# Laser.net
KiCad netlist of a schematic drawn in Altium Designer
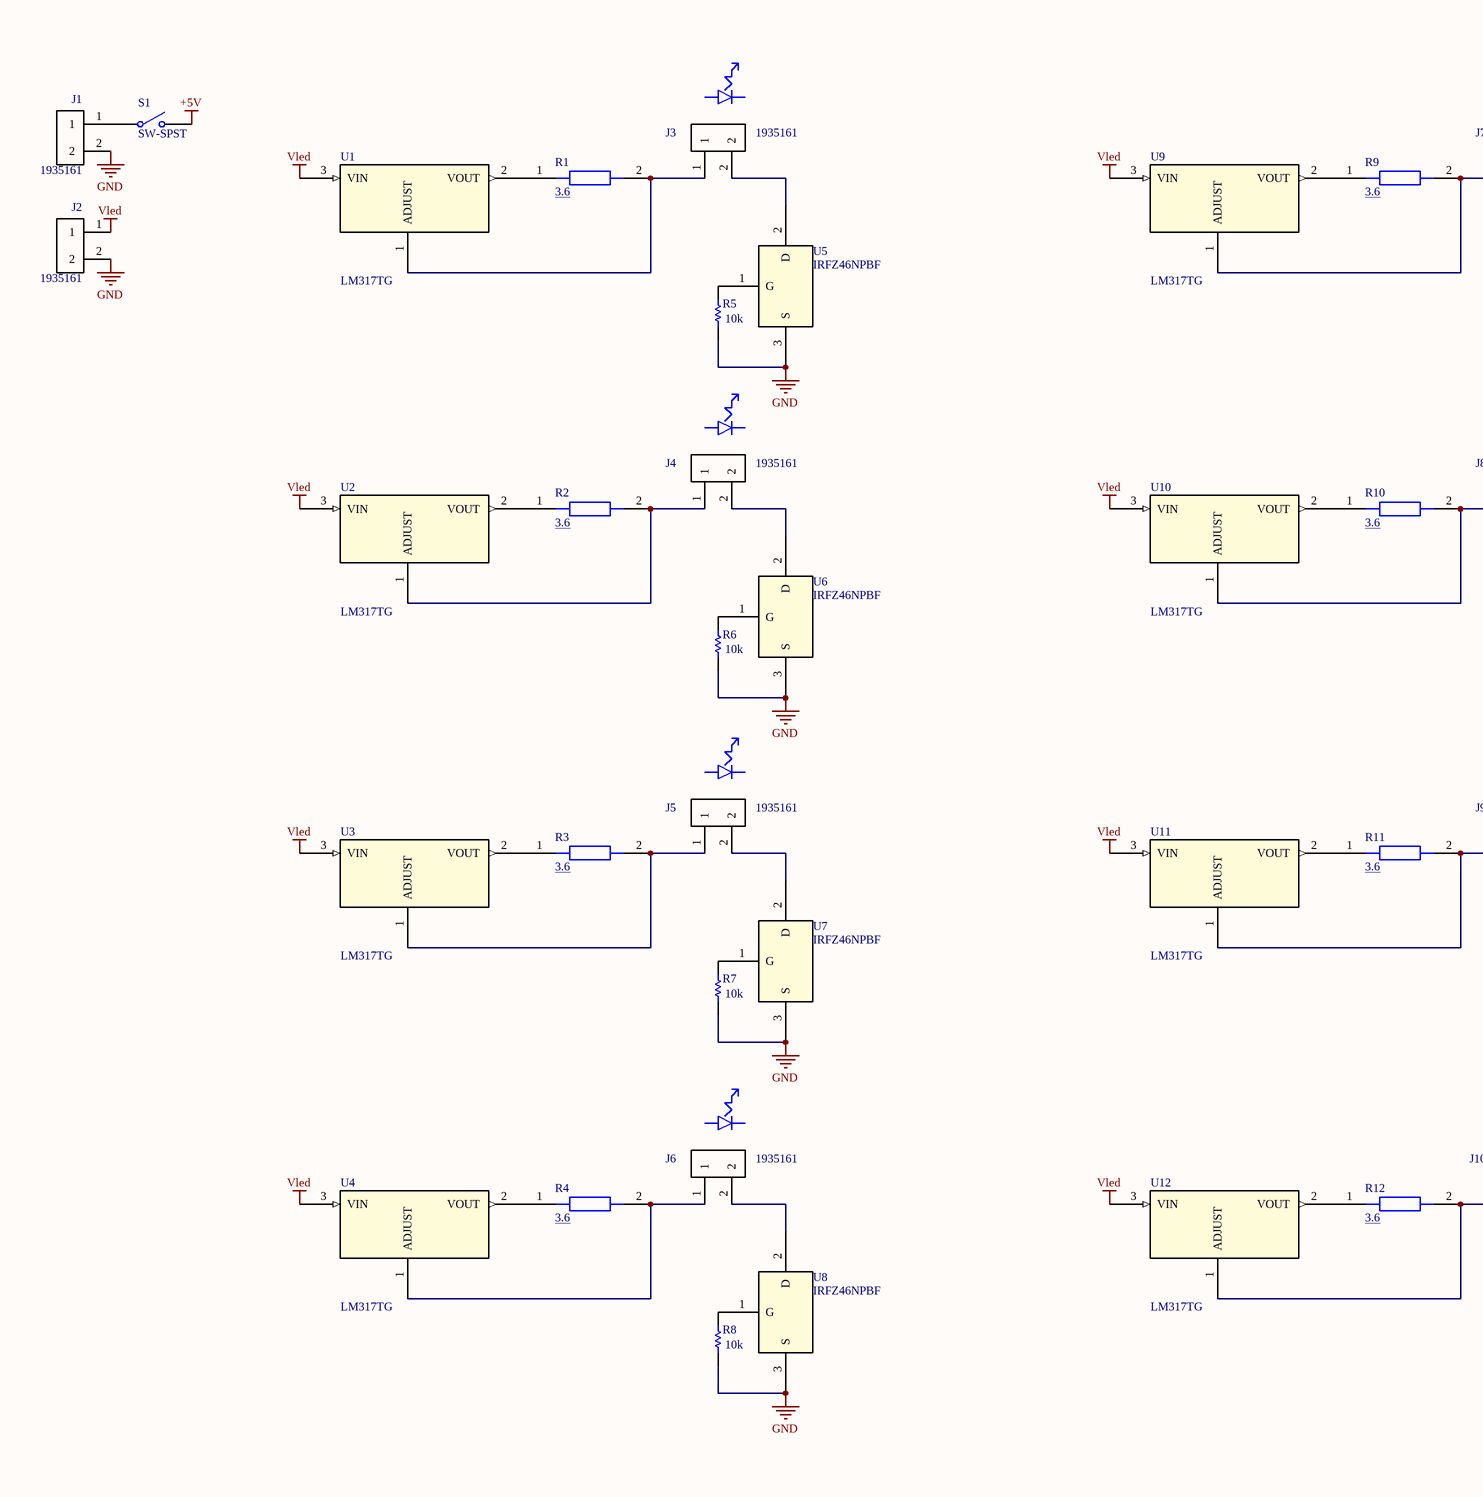
[diagram p0: Laser.SchDoc, left]
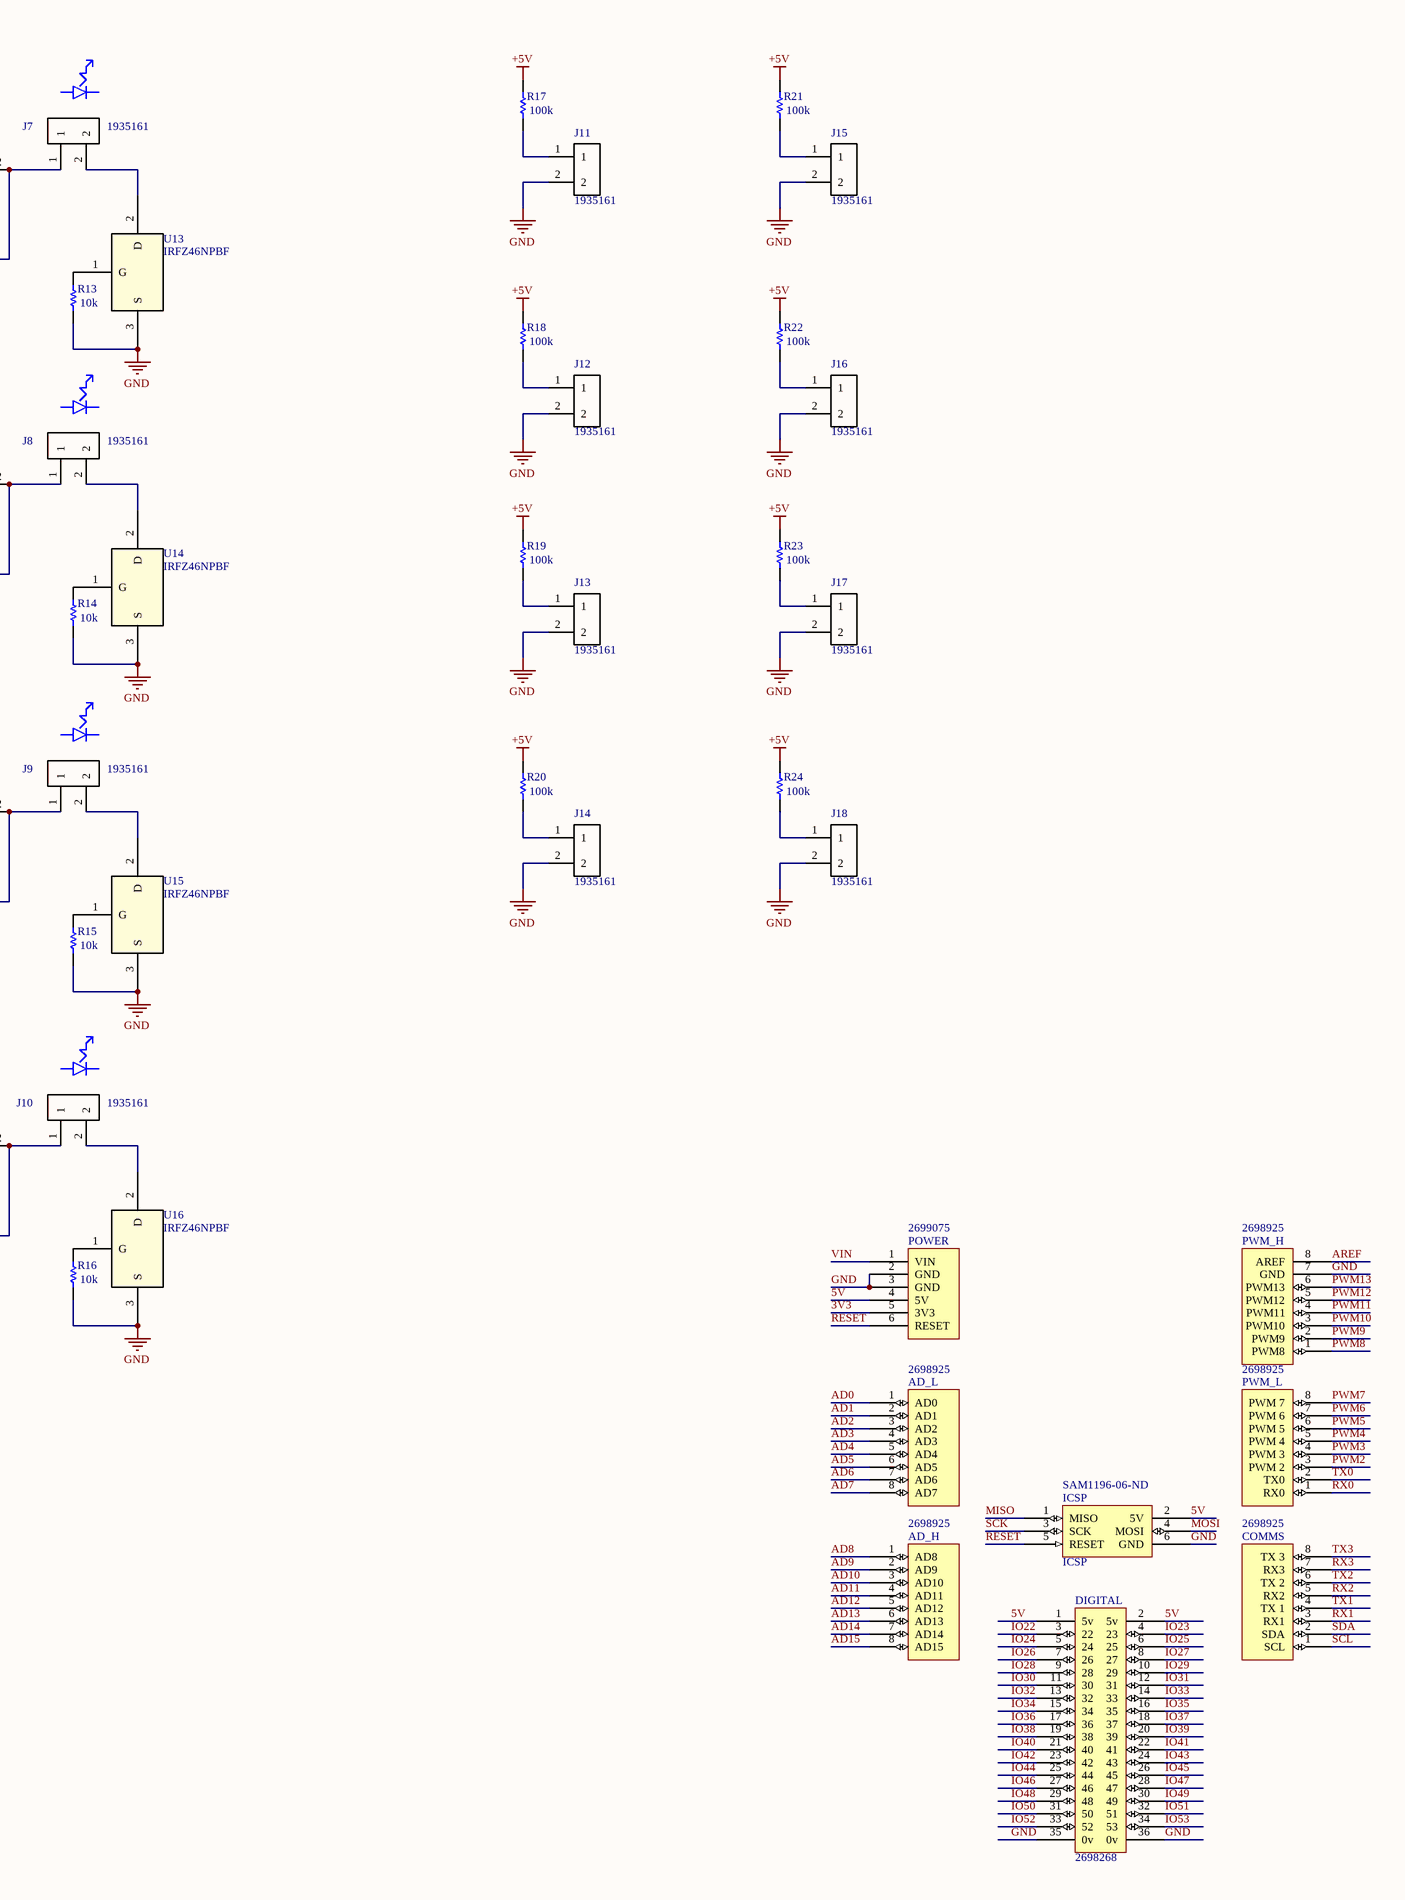
[diagram p1: Laser.SchDoc, right]

(export (version "E")
  (design (tool "Eeschema 10.0.6"))
  (components
    (comp (ref "AD_H")
      (value "AD_H")
      (footprint "Header 8x1 8.5mm")
      (fields (field (name "SUPPLIER PART NUMBER 4") "2698925"))
      (libsource (lib "Header") (part "AD_H"))
    )
    (comp (ref "AD_L")
      (value "AD_L")
      (footprint "Header 8x1 8.5mm")
      (fields (field (name "SUPPLIER PART NUMBER 5") "2698925"))
      (libsource (lib "Header") (part "AD_L"))
    )
    (comp (ref "COMMS")
      (value "Communication")
      (footprint "Header 8x1 8.5mm")
      (fields (field (name "SUPPLIER PART NUMBER 4") "2698925"))
      (libsource (lib "Header") (part "Communication"))
    )
    (comp (ref "DIGITAL")
      (value "IO_36")
      (footprint "HEADER 36X 8MM")
      (fields (field (name "SUPPLIER PART NUMBER 5") "2698268"))
      (libsource (lib "Header") (part "IO_36"))
    )
    (comp (ref "ICSP")
      (value "ICSP")
      (footprint "ICSP")
      (fields (field (name "SUPPLIER PART NUMBER 5") "SAM1196-06-ND"))
      (libsource (lib "Header") (part "ICSP"))
    )
    (comp (ref "J1")
      (value "1935161")
      (footprint "PHOENIX_1935161")
      (description "Conn Terminal Blocks 2 POS 5mm Solder ST Thru-Hole 16A")
      (fields (field (name "DIGI-KEY_PART_NUMBER") "277-1667-ND") (field (name "MF") "Phoenix Contact"))
      (libsource (lib "Laser") (part "1935161"))
    )
    (comp (ref "J2")
      (value "1935161")
      (footprint "PHOENIX_1935161")
      (description "Conn Terminal Blocks 2 POS 5mm Solder ST Thru-Hole 16A")
      (fields (field (name "DIGI-KEY_PART_NUMBER") "277-1667-ND") (field (name "MF") "Phoenix Contact"))
      (libsource (lib "Laser") (part "1935161"))
    )
    (comp (ref "J3")
      (value "1935161")
      (footprint "PHOENIX_1935161")
      (description "Conn Terminal Blocks 2 POS 5mm Solder ST Thru-Hole 16A")
      (fields (field (name "DIGI-KEY_PART_NUMBER") "277-1667-ND") (field (name "MF") "Phoenix Contact"))
      (libsource (lib "Laser") (part "1935161"))
    )
    (comp (ref "J4")
      (value "1935161")
      (footprint "PHOENIX_1935161")
      (description "Conn Terminal Blocks 2 POS 5mm Solder ST Thru-Hole 16A")
      (fields (field (name "DIGI-KEY_PART_NUMBER") "277-1667-ND") (field (name "MF") "Phoenix Contact"))
      (libsource (lib "Laser") (part "1935161"))
    )
    (comp (ref "J5")
      (value "1935161")
      (footprint "PHOENIX_1935161")
      (description "Conn Terminal Blocks 2 POS 5mm Solder ST Thru-Hole 16A")
      (fields (field (name "DIGI-KEY_PART_NUMBER") "277-1667-ND") (field (name "MF") "Phoenix Contact"))
      (libsource (lib "Laser") (part "1935161"))
    )
    (comp (ref "J6")
      (value "1935161")
      (footprint "PHOENIX_1935161")
      (description "Conn Terminal Blocks 2 POS 5mm Solder ST Thru-Hole 16A")
      (fields (field (name "DIGI-KEY_PART_NUMBER") "277-1667-ND") (field (name "MF") "Phoenix Contact"))
      (libsource (lib "Laser") (part "1935161"))
    )
    (comp (ref "J7")
      (value "1935161")
      (footprint "PHOENIX_1935161")
      (description "Conn Terminal Blocks 2 POS 5mm Solder ST Thru-Hole 16A")
      (fields (field (name "DIGI-KEY_PART_NUMBER") "277-1667-ND") (field (name "MF") "Phoenix Contact"))
      (libsource (lib "Laser") (part "1935161"))
    )
    (comp (ref "J8")
      (value "1935161")
      (footprint "PHOENIX_1935161")
      (description "Conn Terminal Blocks 2 POS 5mm Solder ST Thru-Hole 16A")
      (fields (field (name "DIGI-KEY_PART_NUMBER") "277-1667-ND") (field (name "MF") "Phoenix Contact"))
      (libsource (lib "Laser") (part "1935161"))
    )
    (comp (ref "J9")
      (value "1935161")
      (footprint "PHOENIX_1935161")
      (description "Conn Terminal Blocks 2 POS 5mm Solder ST Thru-Hole 16A")
      (fields (field (name "DIGI-KEY_PART_NUMBER") "277-1667-ND") (field (name "MF") "Phoenix Contact"))
      (libsource (lib "Laser") (part "1935161"))
    )
    (comp (ref "J10")
      (value "1935161")
      (footprint "PHOENIX_1935161")
      (description "Conn Terminal Blocks 2 POS 5mm Solder ST Thru-Hole 16A")
      (fields (field (name "DIGI-KEY_PART_NUMBER") "277-1667-ND") (field (name "MF") "Phoenix Contact"))
      (libsource (lib "Laser") (part "1935161"))
    )
    (comp (ref "J11")
      (value "1935161")
      (footprint "PHOENIX_1935161")
      (description "Conn Terminal Blocks 2 POS 5mm Solder ST Thru-Hole 16A")
      (fields (field (name "DIGI-KEY_PART_NUMBER") "277-1667-ND") (field (name "MF") "Phoenix Contact"))
      (libsource (lib "Laser") (part "1935161"))
    )
    (comp (ref "J12")
      (value "1935161")
      (footprint "PHOENIX_1935161")
      (description "Conn Terminal Blocks 2 POS 5mm Solder ST Thru-Hole 16A")
      (fields (field (name "DIGI-KEY_PART_NUMBER") "277-1667-ND") (field (name "MF") "Phoenix Contact"))
      (libsource (lib "Laser") (part "1935161"))
    )
    (comp (ref "J13")
      (value "1935161")
      (footprint "PHOENIX_1935161")
      (description "Conn Terminal Blocks 2 POS 5mm Solder ST Thru-Hole 16A")
      (fields (field (name "DIGI-KEY_PART_NUMBER") "277-1667-ND") (field (name "MF") "Phoenix Contact"))
      (libsource (lib "Laser") (part "1935161"))
    )
    (comp (ref "J14")
      (value "1935161")
      (footprint "PHOENIX_1935161")
      (description "Conn Terminal Blocks 2 POS 5mm Solder ST Thru-Hole 16A")
      (fields (field (name "DIGI-KEY_PART_NUMBER") "277-1667-ND") (field (name "MF") "Phoenix Contact"))
      (libsource (lib "Laser") (part "1935161"))
    )
    (comp (ref "J15")
      (value "1935161")
      (footprint "PHOENIX_1935161")
      (description "Conn Terminal Blocks 2 POS 5mm Solder ST Thru-Hole 16A")
      (fields (field (name "DIGI-KEY_PART_NUMBER") "277-1667-ND") (field (name "MF") "Phoenix Contact"))
      (libsource (lib "Laser") (part "1935161"))
    )
    (comp (ref "J16")
      (value "1935161")
      (footprint "PHOENIX_1935161")
      (description "Conn Terminal Blocks 2 POS 5mm Solder ST Thru-Hole 16A")
      (fields (field (name "DIGI-KEY_PART_NUMBER") "277-1667-ND") (field (name "MF") "Phoenix Contact"))
      (libsource (lib "Laser") (part "1935161"))
    )
    (comp (ref "J17")
      (value "1935161")
      (footprint "PHOENIX_1935161")
      (description "Conn Terminal Blocks 2 POS 5mm Solder ST Thru-Hole 16A")
      (fields (field (name "DIGI-KEY_PART_NUMBER") "277-1667-ND") (field (name "MF") "Phoenix Contact"))
      (libsource (lib "Laser") (part "1935161"))
    )
    (comp (ref "J18")
      (value "1935161")
      (footprint "PHOENIX_1935161")
      (description "Conn Terminal Blocks 2 POS 5mm Solder ST Thru-Hole 16A")
      (fields (field (name "DIGI-KEY_PART_NUMBER") "277-1667-ND") (field (name "MF") "Phoenix Contact"))
      (libsource (lib "Laser") (part "1935161"))
    )
    (comp (ref "POWER")
      (value "POWER")
      (footprint "Header 6x1 8.5mm")
      (fields (field (name "SUPPLIER PART NUMBER 2") "2699075"))
      (libsource (lib "Header") (part "POWER"))
    )
    (comp (ref "PWM_H")
      (value "PWM_H")
      (footprint "Header 8x1 8.5mm")
      (fields (field (name "SUPPLIER PART NUMBER 4") "2698925"))
      (libsource (lib "Header") (part "PWM_H"))
    )
    (comp (ref "PWM_L")
      (value "PWM_L")
      (footprint "Header 8x1 8.5mm")
      (fields (field (name "SUPPLIER PART NUMBER 4") "2698925"))
      (libsource (lib "Header") (part "PWM_L"))
    )
    (comp (ref "R1") (value "3.6") (footprint "3.6_R") (libsource (lib "Laser") (part "3.6")))
    (comp (ref "R2") (value "3.6") (footprint "3.6_R") (libsource (lib "Laser") (part "3.6")))
    (comp (ref "R3") (value "3.6") (footprint "3.6_R") (libsource (lib "Laser") (part "3.6")))
    (comp (ref "R4") (value "3.6") (footprint "3.6_R") (libsource (lib "Laser") (part "3.6")))
    (comp (ref "R5")
      (value "10k")
      (footprint "AXIAL-0.3")
      (description "Resistor")
      (fields (field (name "Comment") "Res1") (field (name "PUBLISHER") "Altium Limited"))
      (libsource (lib "Miscellaneous Devices") (part "Res1"))
    )
    (comp (ref "R6")
      (value "10k")
      (footprint "AXIAL-0.3")
      (description "Resistor")
      (fields (field (name "Comment") "Res1") (field (name "PUBLISHER") "Altium Limited"))
      (libsource (lib "Miscellaneous Devices") (part "Res1"))
    )
    (comp (ref "R7")
      (value "10k")
      (footprint "AXIAL-0.3")
      (description "Resistor")
      (fields (field (name "Comment") "Res1") (field (name "PUBLISHER") "Altium Limited"))
      (libsource (lib "Miscellaneous Devices") (part "Res1"))
    )
    (comp (ref "R8")
      (value "10k")
      (footprint "AXIAL-0.3")
      (description "Resistor")
      (fields (field (name "Comment") "Res1") (field (name "PUBLISHER") "Altium Limited"))
      (libsource (lib "Miscellaneous Devices") (part "Res1"))
    )
    (comp (ref "R9") (value "3.6") (footprint "3.6_R") (libsource (lib "Laser") (part "3.6")))
    (comp (ref "R10") (value "3.6") (footprint "3.6_R") (libsource (lib "Laser") (part "3.6")))
    (comp (ref "R11") (value "3.6") (footprint "3.6_R") (libsource (lib "Laser") (part "3.6")))
    (comp (ref "R12") (value "3.6") (footprint "3.6_R") (libsource (lib "Laser") (part "3.6")))
    (comp (ref "R13")
      (value "10k")
      (footprint "AXIAL-0.3")
      (description "Resistor")
      (fields (field (name "Comment") "Res1") (field (name "PUBLISHER") "Altium Limited"))
      (libsource (lib "Miscellaneous Devices") (part "Res1"))
    )
    (comp (ref "R14")
      (value "10k")
      (footprint "AXIAL-0.3")
      (description "Resistor")
      (fields (field (name "Comment") "Res1") (field (name "PUBLISHER") "Altium Limited"))
      (libsource (lib "Miscellaneous Devices") (part "Res1"))
    )
    (comp (ref "R15")
      (value "10k")
      (footprint "AXIAL-0.3")
      (description "Resistor")
      (fields (field (name "Comment") "Res1") (field (name "PUBLISHER") "Altium Limited"))
      (libsource (lib "Miscellaneous Devices") (part "Res1"))
    )
    (comp (ref "R16")
      (value "10k")
      (footprint "AXIAL-0.3")
      (description "Resistor")
      (fields (field (name "Comment") "Res1") (field (name "PUBLISHER") "Altium Limited"))
      (libsource (lib "Miscellaneous Devices") (part "Res1"))
    )
    (comp (ref "R17")
      (value "100k")
      (footprint "AXIAL-0.3")
      (description "Resistor")
      (fields (field (name "Comment") "Res1") (field (name "PUBLISHER") "Altium Limited"))
      (libsource (lib "Miscellaneous Devices") (part "Res1"))
    )
    (comp (ref "R18")
      (value "100k")
      (footprint "AXIAL-0.3")
      (description "Resistor")
      (fields (field (name "Comment") "Res1") (field (name "PUBLISHER") "Altium Limited"))
      (libsource (lib "Miscellaneous Devices") (part "Res1"))
    )
    (comp (ref "R19")
      (value "100k")
      (footprint "AXIAL-0.3")
      (description "Resistor")
      (fields (field (name "Comment") "Res1") (field (name "PUBLISHER") "Altium Limited"))
      (libsource (lib "Miscellaneous Devices") (part "Res1"))
    )
    (comp (ref "R20")
      (value "100k")
      (footprint "AXIAL-0.3")
      (description "Resistor")
      (fields (field (name "Comment") "Res1") (field (name "PUBLISHER") "Altium Limited"))
      (libsource (lib "Miscellaneous Devices") (part "Res1"))
    )
    (comp (ref "R21")
      (value "100k")
      (footprint "AXIAL-0.3")
      (description "Resistor")
      (fields (field (name "Comment") "Res1") (field (name "PUBLISHER") "Altium Limited"))
      (libsource (lib "Miscellaneous Devices") (part "Res1"))
    )
    (comp (ref "R22")
      (value "100k")
      (footprint "AXIAL-0.3")
      (description "Resistor")
      (fields (field (name "Comment") "Res1") (field (name "PUBLISHER") "Altium Limited"))
      (libsource (lib "Miscellaneous Devices") (part "Res1"))
    )
    (comp (ref "R23")
      (value "100k")
      (footprint "AXIAL-0.3")
      (description "Resistor")
      (fields (field (name "Comment") "Res1") (field (name "PUBLISHER") "Altium Limited"))
      (libsource (lib "Miscellaneous Devices") (part "Res1"))
    )
    (comp (ref "R24")
      (value "100k")
      (footprint "AXIAL-0.3")
      (description "Resistor")
      (fields (field (name "Comment") "Res1") (field (name "PUBLISHER") "Altium Limited"))
      (libsource (lib "Miscellaneous Devices") (part "Res1"))
    )
    (comp (ref "S1")
      (value "SW-SPST")
      (footprint "SPST-2")
      (description "Single-Pole, Single-Throw Switch")
      (fields (field (name "PUBLISHER") "Altium Limited"))
      (libsource (lib "Miscellaneous Devices") (part "SW-SPST"))
    )
    (comp (ref "U1")
      (value "LM317TG")
      (footprint "TO-220AB")
      (description "Imported")
      (libsource (lib "Laser") (part "LM317TG"))
    )
    (comp (ref "U2")
      (value "LM317TG")
      (footprint "TO-220AB")
      (description "Imported")
      (libsource (lib "Laser") (part "LM317TG"))
    )
    (comp (ref "U3")
      (value "LM317TG")
      (footprint "TO-220AB")
      (description "Imported")
      (libsource (lib "Laser") (part "LM317TG"))
    )
    (comp (ref "U4")
      (value "LM317TG")
      (footprint "TO-220AB")
      (description "Imported")
      (libsource (lib "Laser") (part "LM317TG"))
    )
    (comp (ref "U5")
      (value "IRFZ46NPBF")
      (footprint "TO-220AB")
      (description "Imported")
      (libsource (lib "Laser") (part "IRFZ46NPBF"))
    )
    (comp (ref "U6")
      (value "IRFZ46NPBF")
      (footprint "TO-220AB")
      (description "Imported")
      (libsource (lib "Laser") (part "IRFZ46NPBF"))
    )
    (comp (ref "U7")
      (value "IRFZ46NPBF")
      (footprint "TO-220AB")
      (description "Imported")
      (libsource (lib "Laser") (part "IRFZ46NPBF"))
    )
    (comp (ref "U8")
      (value "IRFZ46NPBF")
      (footprint "TO-220AB")
      (description "Imported")
      (libsource (lib "Laser") (part "IRFZ46NPBF"))
    )
    (comp (ref "U9")
      (value "LM317TG")
      (footprint "TO-220AB")
      (description "Imported")
      (libsource (lib "Laser") (part "LM317TG"))
    )
    (comp (ref "U10")
      (value "LM317TG")
      (footprint "TO-220AB")
      (description "Imported")
      (libsource (lib "Laser") (part "LM317TG"))
    )
    (comp (ref "U11")
      (value "LM317TG")
      (footprint "TO-220AB")
      (description "Imported")
      (libsource (lib "Laser") (part "LM317TG"))
    )
    (comp (ref "U12")
      (value "LM317TG")
      (footprint "TO-220AB")
      (description "Imported")
      (libsource (lib "Laser") (part "LM317TG"))
    )
    (comp (ref "U13")
      (value "IRFZ46NPBF")
      (footprint "TO-220AB")
      (description "Imported")
      (libsource (lib "Laser") (part "IRFZ46NPBF"))
    )
    (comp (ref "U14")
      (value "IRFZ46NPBF")
      (footprint "TO-220AB")
      (description "Imported")
      (libsource (lib "Laser") (part "IRFZ46NPBF"))
    )
    (comp (ref "U15")
      (value "IRFZ46NPBF")
      (footprint "TO-220AB")
      (description "Imported")
      (libsource (lib "Laser") (part "IRFZ46NPBF"))
    )
    (comp (ref "U16")
      (value "IRFZ46NPBF")
      (footprint "TO-220AB")
      (description "Imported")
      (libsource (lib "Laser") (part "IRFZ46NPBF"))
    )
  )
  (nets
    (net (code "1") (name "+5V") (class "Default")
      (node (ref "R17") (pin "2") (pinfunction "2_2") (pintype "passive"))
      (node (ref "R18") (pin "2") (pinfunction "2_2") (pintype "passive"))
      (node (ref "R19") (pin "2") (pinfunction "2_2") (pintype "passive"))
      (node (ref "R20") (pin "2") (pinfunction "2_2") (pintype "passive"))
      (node (ref "R21") (pin "2") (pinfunction "2_2") (pintype "passive"))
      (node (ref "R22") (pin "2") (pinfunction "2_2") (pintype "passive"))
      (node (ref "R23") (pin "2") (pinfunction "2_2") (pintype "passive"))
      (node (ref "R24") (pin "2") (pinfunction "2_2") (pintype "passive"))
      (node (ref "S1") (pin "2") (pinfunction "NO_2") (pintype "passive"))
    )
    (net (code "2") (name "/3V3") (class "Default")
      (node (ref "POWER") (pin "5") (pinfunction "3V3_5") (pintype "power_in"))
    )
    (net (code "3") (name "/5V") (class "Default")
      (node (ref "DIGITAL") (pin "1") (pinfunction "5v_1") (pintype "power_in"))
      (node (ref "DIGITAL") (pin "2") (pinfunction "5v_2") (pintype "power_in"))
      (node (ref "ICSP") (pin "2") (pinfunction "5V_2") (pintype "power_in"))
      (node (ref "POWER") (pin "4") (pinfunction "5V_4") (pintype "power_in"))
    )
    (net (code "4") (name "/AD0") (class "Default")
      (node (ref "AD_L") (pin "1") (pinfunction "AD0_1") (pintype "bidirectional"))
    )
    (net (code "5") (name "/AD1") (class "Default")
      (node (ref "AD_L") (pin "2") (pinfunction "AD1_2") (pintype "bidirectional"))
    )
    (net (code "6") (name "/AD2") (class "Default")
      (node (ref "AD_L") (pin "3") (pinfunction "AD2_3") (pintype "bidirectional"))
    )
    (net (code "7") (name "/AD3") (class "Default")
      (node (ref "AD_L") (pin "4") (pinfunction "AD3_4") (pintype "bidirectional"))
    )
    (net (code "8") (name "/AD4") (class "Default")
      (node (ref "AD_L") (pin "5") (pinfunction "AD4_5") (pintype "bidirectional"))
    )
    (net (code "9") (name "/AD5") (class "Default")
      (node (ref "AD_L") (pin "6") (pinfunction "AD5_6") (pintype "bidirectional"))
    )
    (net (code "10") (name "/AD6") (class "Default")
      (node (ref "AD_L") (pin "7") (pinfunction "AD6_7") (pintype "bidirectional"))
    )
    (net (code "11") (name "/AD7") (class "Default")
      (node (ref "AD_L") (pin "8") (pinfunction "AD7_8") (pintype "bidirectional"))
    )
    (net (code "12") (name "/AD8") (class "Default")
      (node (ref "AD_H") (pin "1") (pinfunction "AD8_1") (pintype "bidirectional"))
    )
    (net (code "13") (name "/AD9") (class "Default")
      (node (ref "AD_H") (pin "2") (pinfunction "AD9_2") (pintype "bidirectional"))
    )
    (net (code "14") (name "/AD10") (class "Default")
      (node (ref "AD_H") (pin "3") (pinfunction "AD10_3") (pintype "bidirectional"))
    )
    (net (code "15") (name "/AD11") (class "Default")
      (node (ref "AD_H") (pin "4") (pinfunction "AD11_4") (pintype "bidirectional"))
    )
    (net (code "16") (name "/AD12") (class "Default")
      (node (ref "AD_H") (pin "5") (pinfunction "AD12_5") (pintype "bidirectional"))
    )
    (net (code "17") (name "/AD13") (class "Default")
      (node (ref "AD_H") (pin "6") (pinfunction "AD13_6") (pintype "bidirectional"))
    )
    (net (code "18") (name "/AD14") (class "Default")
      (node (ref "AD_H") (pin "7") (pinfunction "AD14_7") (pintype "bidirectional"))
    )
    (net (code "19") (name "/AD15") (class "Default")
      (node (ref "AD_H") (pin "8") (pinfunction "AD15_8") (pintype "bidirectional"))
    )
    (net (code "20") (name "/AREF") (class "Default")
      (node (ref "PWM_H") (pin "8") (pinfunction "AREF_8") (pintype "passive"))
    )
    (net (code "21") (name "/IO22") (class "Default")
      (node (ref "DIGITAL") (pin "3") (pinfunction "22_3") (pintype "bidirectional"))
    )
    (net (code "22") (name "/IO23") (class "Default")
      (node (ref "DIGITAL") (pin "4") (pinfunction "23_4") (pintype "bidirectional"))
    )
    (net (code "23") (name "/IO24") (class "Default")
      (node (ref "DIGITAL") (pin "5") (pinfunction "24_5") (pintype "bidirectional"))
    )
    (net (code "24") (name "/IO25") (class "Default")
      (node (ref "DIGITAL") (pin "6") (pinfunction "25_6") (pintype "bidirectional"))
    )
    (net (code "25") (name "/IO26") (class "Default")
      (node (ref "DIGITAL") (pin "7") (pinfunction "26_7") (pintype "bidirectional"))
    )
    (net (code "26") (name "/IO27") (class "Default")
      (node (ref "DIGITAL") (pin "8") (pinfunction "27_8") (pintype "bidirectional"))
    )
    (net (code "27") (name "/IO28") (class "Default")
      (node (ref "DIGITAL") (pin "9") (pinfunction "28_9") (pintype "bidirectional"))
    )
    (net (code "28") (name "/IO29") (class "Default")
      (node (ref "DIGITAL") (pin "10") (pinfunction "29_10") (pintype "bidirectional"))
    )
    (net (code "29") (name "/IO30") (class "Default")
      (node (ref "DIGITAL") (pin "11") (pinfunction "30_11") (pintype "bidirectional"))
    )
    (net (code "30") (name "/IO31") (class "Default")
      (node (ref "DIGITAL") (pin "12") (pinfunction "31_12") (pintype "bidirectional"))
    )
    (net (code "31") (name "/IO32") (class "Default")
      (node (ref "DIGITAL") (pin "13") (pinfunction "32_13") (pintype "bidirectional"))
    )
    (net (code "32") (name "/IO33") (class "Default")
      (node (ref "DIGITAL") (pin "14") (pinfunction "33_14") (pintype "bidirectional"))
    )
    (net (code "33") (name "/IO34") (class "Default")
      (node (ref "DIGITAL") (pin "15") (pinfunction "34_15") (pintype "bidirectional"))
    )
    (net (code "34") (name "/IO35") (class "Default")
      (node (ref "DIGITAL") (pin "16") (pinfunction "35_16") (pintype "bidirectional"))
    )
    (net (code "35") (name "/IO36") (class "Default")
      (node (ref "DIGITAL") (pin "17") (pinfunction "36_17") (pintype "bidirectional"))
    )
    (net (code "36") (name "/IO37") (class "Default")
      (node (ref "DIGITAL") (pin "18") (pinfunction "37_18") (pintype "bidirectional"))
    )
    (net (code "37") (name "/IO38") (class "Default")
      (node (ref "DIGITAL") (pin "19") (pinfunction "38_19") (pintype "bidirectional"))
    )
    (net (code "38") (name "/IO39") (class "Default")
      (node (ref "DIGITAL") (pin "20") (pinfunction "39_20") (pintype "bidirectional"))
    )
    (net (code "39") (name "/IO40") (class "Default")
      (node (ref "DIGITAL") (pin "21") (pinfunction "40_21") (pintype "bidirectional"))
    )
    (net (code "40") (name "/IO41") (class "Default")
      (node (ref "DIGITAL") (pin "22") (pinfunction "41_22") (pintype "bidirectional"))
    )
    (net (code "41") (name "/IO42") (class "Default")
      (node (ref "DIGITAL") (pin "23") (pinfunction "42_23") (pintype "bidirectional"))
    )
    (net (code "42") (name "/IO43") (class "Default")
      (node (ref "DIGITAL") (pin "24") (pinfunction "43_24") (pintype "bidirectional"))
    )
    (net (code "43") (name "/IO44") (class "Default")
      (node (ref "DIGITAL") (pin "25") (pinfunction "44_25") (pintype "bidirectional"))
    )
    (net (code "44") (name "/IO45") (class "Default")
      (node (ref "DIGITAL") (pin "26") (pinfunction "45_26") (pintype "bidirectional"))
    )
    (net (code "45") (name "/IO46") (class "Default")
      (node (ref "DIGITAL") (pin "27") (pinfunction "46_27") (pintype "bidirectional"))
    )
    (net (code "46") (name "/IO47") (class "Default")
      (node (ref "DIGITAL") (pin "28") (pinfunction "47_28") (pintype "bidirectional"))
    )
    (net (code "47") (name "/IO48") (class "Default")
      (node (ref "DIGITAL") (pin "29") (pinfunction "48_29") (pintype "bidirectional"))
    )
    (net (code "48") (name "/IO49") (class "Default")
      (node (ref "DIGITAL") (pin "30") (pinfunction "49_30") (pintype "bidirectional"))
    )
    (net (code "49") (name "/IO50") (class "Default")
      (node (ref "DIGITAL") (pin "31") (pinfunction "50_31") (pintype "bidirectional"))
    )
    (net (code "50") (name "/IO51") (class "Default")
      (node (ref "DIGITAL") (pin "32") (pinfunction "51_32") (pintype "bidirectional"))
    )
    (net (code "51") (name "/IO52") (class "Default")
      (node (ref "DIGITAL") (pin "33") (pinfunction "52_33") (pintype "bidirectional"))
    )
    (net (code "52") (name "/IO53") (class "Default")
      (node (ref "DIGITAL") (pin "34") (pinfunction "53_34") (pintype "bidirectional"))
    )
    (net (code "53") (name "/MISO") (class "Default")
      (node (ref "ICSP") (pin "1") (pinfunction "MISO_1") (pintype "bidirectional"))
    )
    (net (code "54") (name "/MOSI") (class "Default")
      (node (ref "ICSP") (pin "4") (pinfunction "MOSI_4") (pintype "bidirectional"))
    )
    (net (code "55") (name "/PWM2") (class "Default")
      (node (ref "PWM_L") (pin "3") (pinfunction "PWM_2_3") (pintype "bidirectional"))
    )
    (net (code "56") (name "/PWM3") (class "Default")
      (node (ref "PWM_L") (pin "4") (pinfunction "PWM_3_4") (pintype "bidirectional"))
    )
    (net (code "57") (name "/PWM4") (class "Default")
      (node (ref "PWM_L") (pin "5") (pinfunction "PWM_4_5") (pintype "bidirectional"))
    )
    (net (code "58") (name "/PWM5") (class "Default")
      (node (ref "PWM_L") (pin "6") (pinfunction "PWM_5_6") (pintype "bidirectional"))
    )
    (net (code "59") (name "/PWM6") (class "Default")
      (node (ref "PWM_L") (pin "7") (pinfunction "PWM_6_7") (pintype "bidirectional"))
    )
    (net (code "60") (name "/PWM7") (class "Default")
      (node (ref "PWM_L") (pin "8") (pinfunction "PWM_7_8") (pintype "bidirectional"))
    )
    (net (code "61") (name "/PWM8") (class "Default")
      (node (ref "PWM_H") (pin "1") (pinfunction "PWM8_1") (pintype "bidirectional"))
    )
    (net (code "62") (name "/PWM9") (class "Default")
      (node (ref "PWM_H") (pin "2") (pinfunction "PWM9_2") (pintype "bidirectional"))
    )
    (net (code "63") (name "/PWM10") (class "Default")
      (node (ref "PWM_H") (pin "3") (pinfunction "PWM10_3") (pintype "bidirectional"))
    )
    (net (code "64") (name "/PWM11") (class "Default")
      (node (ref "PWM_H") (pin "4") (pinfunction "PWM11_4") (pintype "bidirectional"))
    )
    (net (code "65") (name "/PWM12") (class "Default")
      (node (ref "PWM_H") (pin "5") (pinfunction "PWM12_5") (pintype "bidirectional"))
    )
    (net (code "66") (name "/PWM13") (class "Default")
      (node (ref "PWM_H") (pin "6") (pinfunction "PWM13_6") (pintype "bidirectional"))
    )
    (net (code "67") (name "/RESET") (class "Default")
      (node (ref "ICSP") (pin "5") (pinfunction "RESET_5") (pintype "input"))
      (node (ref "POWER") (pin "6") (pinfunction "RESET_6") (pintype "passive"))
    )
    (net (code "68") (name "/RX0") (class "Default")
      (node (ref "PWM_L") (pin "1") (pinfunction "RX0_1") (pintype "bidirectional"))
    )
    (net (code "69") (name "/RX1") (class "Default")
      (node (ref "COMMS") (pin "3") (pinfunction "RX1_3") (pintype "bidirectional"))
    )
    (net (code "70") (name "/RX2") (class "Default")
      (node (ref "COMMS") (pin "5") (pinfunction "RX2_5") (pintype "bidirectional"))
    )
    (net (code "71") (name "/RX3") (class "Default")
      (node (ref "COMMS") (pin "7") (pinfunction "RX3_7") (pintype "bidirectional"))
    )
    (net (code "72") (name "/SCK") (class "Default")
      (node (ref "ICSP") (pin "3") (pinfunction "SCK_3") (pintype "bidirectional"))
    )
    (net (code "73") (name "/SCL") (class "Default")
      (node (ref "COMMS") (pin "1") (pinfunction "SCL_1") (pintype "bidirectional"))
    )
    (net (code "74") (name "/SDA") (class "Default")
      (node (ref "COMMS") (pin "2") (pinfunction "SDA_2") (pintype "bidirectional"))
    )
    (net (code "75") (name "/TX0") (class "Default")
      (node (ref "PWM_L") (pin "2") (pinfunction "TX0_2") (pintype "bidirectional"))
    )
    (net (code "76") (name "/TX1") (class "Default")
      (node (ref "COMMS") (pin "4") (pinfunction "TX_1_4") (pintype "bidirectional"))
    )
    (net (code "77") (name "/TX2") (class "Default")
      (node (ref "COMMS") (pin "6") (pinfunction "TX_2_6") (pintype "bidirectional"))
    )
    (net (code "78") (name "/TX3") (class "Default")
      (node (ref "COMMS") (pin "8") (pinfunction "TX_3_8") (pintype "bidirectional"))
    )
    (net (code "79") (name "/VIN") (class "Default")
      (node (ref "POWER") (pin "1") (pinfunction "VIN_1") (pintype "power_in"))
    )
    (net (code "80") (name "GND") (class "Default")
      (node (ref "DIGITAL") (pin "35") (pinfunction "0v_35") (pintype "power_in"))
      (node (ref "DIGITAL") (pin "36") (pinfunction "0v_36") (pintype "power_in"))
      (node (ref "ICSP") (pin "6") (pinfunction "GND_6") (pintype "power_in"))
      (node (ref "J1") (pin "2") (pinfunction "2_2") (pintype "passive"))
      (node (ref "J11") (pin "2") (pinfunction "2_2") (pintype "passive"))
      (node (ref "J12") (pin "2") (pinfunction "2_2") (pintype "passive"))
      (node (ref "J13") (pin "2") (pinfunction "2_2") (pintype "passive"))
      (node (ref "J14") (pin "2") (pinfunction "2_2") (pintype "passive"))
      (node (ref "J15") (pin "2") (pinfunction "2_2") (pintype "passive"))
      (node (ref "J16") (pin "2") (pinfunction "2_2") (pintype "passive"))
      (node (ref "J17") (pin "2") (pinfunction "2_2") (pintype "passive"))
      (node (ref "J18") (pin "2") (pinfunction "2_2") (pintype "passive"))
      (node (ref "J2") (pin "2") (pinfunction "2_2") (pintype "passive"))
      (node (ref "POWER") (pin "2") (pinfunction "GND_2") (pintype "power_in"))
      (node (ref "POWER") (pin "3") (pinfunction "GND_3") (pintype "power_in"))
      (node (ref "PWM_H") (pin "7") (pinfunction "GND_7") (pintype "power_in"))
      (node (ref "R13") (pin "1") (pinfunction "1_1") (pintype "passive"))
      (node (ref "R14") (pin "1") (pinfunction "1_1") (pintype "passive"))
      (node (ref "R15") (pin "1") (pinfunction "1_1") (pintype "passive"))
      (node (ref "R16") (pin "1") (pinfunction "1_1") (pintype "passive"))
      (node (ref "R5") (pin "1") (pinfunction "1_1") (pintype "passive"))
      (node (ref "R6") (pin "1") (pinfunction "1_1") (pintype "passive"))
      (node (ref "R7") (pin "1") (pinfunction "1_1") (pintype "passive"))
      (node (ref "R8") (pin "1") (pinfunction "1_1") (pintype "passive"))
      (node (ref "U13") (pin "3") (pinfunction "S_3") (pintype "passive"))
      (node (ref "U14") (pin "3") (pinfunction "S_3") (pintype "passive"))
      (node (ref "U15") (pin "3") (pinfunction "S_3") (pintype "passive"))
      (node (ref "U16") (pin "3") (pinfunction "S_3") (pintype "passive"))
      (node (ref "U5") (pin "3") (pinfunction "S_3") (pintype "passive"))
      (node (ref "U6") (pin "3") (pinfunction "S_3") (pintype "passive"))
      (node (ref "U7") (pin "3") (pinfunction "S_3") (pintype "passive"))
      (node (ref "U8") (pin "3") (pinfunction "S_3") (pintype "passive"))
    )
    (net (code "81") (name "Net-(J11-Pad1)") (class "Default")
      (node (ref "J11") (pin "1") (pinfunction "1_1") (pintype "passive"))
      (node (ref "R17") (pin "1") (pinfunction "1_1") (pintype "passive"))
    )
    (net (code "82") (name "Net-(J12-Pad1)") (class "Default")
      (node (ref "J12") (pin "1") (pinfunction "1_1") (pintype "passive"))
      (node (ref "R18") (pin "1") (pinfunction "1_1") (pintype "passive"))
    )
    (net (code "83") (name "Net-(J13-Pad1)") (class "Default")
      (node (ref "J13") (pin "1") (pinfunction "1_1") (pintype "passive"))
      (node (ref "R19") (pin "1") (pinfunction "1_1") (pintype "passive"))
    )
    (net (code "84") (name "Net-(J14-Pad1)") (class "Default")
      (node (ref "J14") (pin "1") (pinfunction "1_1") (pintype "passive"))
      (node (ref "R20") (pin "1") (pinfunction "1_1") (pintype "passive"))
    )
    (net (code "85") (name "Net-(J15-Pad1)") (class "Default")
      (node (ref "J15") (pin "1") (pinfunction "1_1") (pintype "passive"))
      (node (ref "R21") (pin "1") (pinfunction "1_1") (pintype "passive"))
    )
    (net (code "86") (name "Net-(J16-Pad1)") (class "Default")
      (node (ref "J16") (pin "1") (pinfunction "1_1") (pintype "passive"))
      (node (ref "R22") (pin "1") (pinfunction "1_1") (pintype "passive"))
    )
    (net (code "87") (name "Net-(J17-Pad1)") (class "Default")
      (node (ref "J17") (pin "1") (pinfunction "1_1") (pintype "passive"))
      (node (ref "R23") (pin "1") (pinfunction "1_1") (pintype "passive"))
    )
    (net (code "88") (name "Net-(J18-Pad1)") (class "Default")
      (node (ref "J18") (pin "1") (pinfunction "1_1") (pintype "passive"))
      (node (ref "R24") (pin "1") (pinfunction "1_1") (pintype "passive"))
    )
    (net (code "89") (name "Net-(S1-COMMON)") (class "Default")
      (node (ref "J1") (pin "1") (pinfunction "1_1") (pintype "passive"))
      (node (ref "S1") (pin "1") (pinfunction "COMMON_1") (pintype "passive"))
    )
    (net (code "90") (name "Net-(U1-ADJUST)") (class "Default")
      (node (ref "J3") (pin "1") (pinfunction "1_1") (pintype "passive"))
      (node (ref "R1") (pin "2") (pinfunction "2_2") (pintype "passive"))
      (node (ref "U1") (pin "1") (pinfunction "ADJUST_1") (pintype "passive"))
    )
    (net (code "91") (name "Net-(U1-VOUT)") (class "Default")
      (node (ref "R1") (pin "1") (pinfunction "1_1") (pintype "passive"))
      (node (ref "U1") (pin "2") (pinfunction "VOUT_2") (pintype "output"))
    )
    (net (code "92") (name "Net-(U2-ADJUST)") (class "Default")
      (node (ref "J4") (pin "1") (pinfunction "1_1") (pintype "passive"))
      (node (ref "R2") (pin "2") (pinfunction "2_2") (pintype "passive"))
      (node (ref "U2") (pin "1") (pinfunction "ADJUST_1") (pintype "passive"))
    )
    (net (code "93") (name "Net-(U2-VOUT)") (class "Default")
      (node (ref "R2") (pin "1") (pinfunction "1_1") (pintype "passive"))
      (node (ref "U2") (pin "2") (pinfunction "VOUT_2") (pintype "output"))
    )
    (net (code "94") (name "Net-(U3-ADJUST)") (class "Default")
      (node (ref "J5") (pin "1") (pinfunction "1_1") (pintype "passive"))
      (node (ref "R3") (pin "2") (pinfunction "2_2") (pintype "passive"))
      (node (ref "U3") (pin "1") (pinfunction "ADJUST_1") (pintype "passive"))
    )
    (net (code "95") (name "Net-(U3-VOUT)") (class "Default")
      (node (ref "R3") (pin "1") (pinfunction "1_1") (pintype "passive"))
      (node (ref "U3") (pin "2") (pinfunction "VOUT_2") (pintype "output"))
    )
    (net (code "96") (name "Net-(U4-ADJUST)") (class "Default")
      (node (ref "J6") (pin "1") (pinfunction "1_1") (pintype "passive"))
      (node (ref "R4") (pin "2") (pinfunction "2_2") (pintype "passive"))
      (node (ref "U4") (pin "1") (pinfunction "ADJUST_1") (pintype "passive"))
    )
    (net (code "97") (name "Net-(U4-VOUT)") (class "Default")
      (node (ref "R4") (pin "1") (pinfunction "1_1") (pintype "passive"))
      (node (ref "U4") (pin "2") (pinfunction "VOUT_2") (pintype "output"))
    )
    (net (code "98") (name "Net-(U5-D)") (class "Default")
      (node (ref "J3") (pin "2") (pinfunction "2_2") (pintype "passive"))
      (node (ref "U5") (pin "2") (pinfunction "D_2") (pintype "passive"))
    )
    (net (code "99") (name "Net-(U5-G)") (class "Default")
      (node (ref "R5") (pin "2") (pinfunction "2_2") (pintype "passive"))
      (node (ref "U5") (pin "1") (pinfunction "G_1") (pintype "passive"))
    )
    (net (code "100") (name "Net-(U6-D)") (class "Default")
      (node (ref "J4") (pin "2") (pinfunction "2_2") (pintype "passive"))
      (node (ref "U6") (pin "2") (pinfunction "D_2") (pintype "passive"))
    )
    (net (code "101") (name "Net-(U6-G)") (class "Default")
      (node (ref "R6") (pin "2") (pinfunction "2_2") (pintype "passive"))
      (node (ref "U6") (pin "1") (pinfunction "G_1") (pintype "passive"))
    )
    (net (code "102") (name "Net-(U7-D)") (class "Default")
      (node (ref "J5") (pin "2") (pinfunction "2_2") (pintype "passive"))
      (node (ref "U7") (pin "2") (pinfunction "D_2") (pintype "passive"))
    )
    (net (code "103") (name "Net-(U7-G)") (class "Default")
      (node (ref "R7") (pin "2") (pinfunction "2_2") (pintype "passive"))
      (node (ref "U7") (pin "1") (pinfunction "G_1") (pintype "passive"))
    )
    (net (code "104") (name "Net-(U8-D)") (class "Default")
      (node (ref "J6") (pin "2") (pinfunction "2_2") (pintype "passive"))
      (node (ref "U8") (pin "2") (pinfunction "D_2") (pintype "passive"))
    )
    (net (code "105") (name "Net-(U8-G)") (class "Default")
      (node (ref "R8") (pin "2") (pinfunction "2_2") (pintype "passive"))
      (node (ref "U8") (pin "1") (pinfunction "G_1") (pintype "passive"))
    )
    (net (code "106") (name "Net-(U9-ADJUST)") (class "Default")
      (node (ref "J7") (pin "1") (pinfunction "1_1") (pintype "passive"))
      (node (ref "R9") (pin "2") (pinfunction "2_2") (pintype "passive"))
      (node (ref "U9") (pin "1") (pinfunction "ADJUST_1") (pintype "passive"))
    )
    (net (code "107") (name "Net-(U9-VOUT)") (class "Default")
      (node (ref "R9") (pin "1") (pinfunction "1_1") (pintype "passive"))
      (node (ref "U9") (pin "2") (pinfunction "VOUT_2") (pintype "output"))
    )
    (net (code "108") (name "Net-(U10-ADJUST)") (class "Default")
      (node (ref "J8") (pin "1") (pinfunction "1_1") (pintype "passive"))
      (node (ref "R10") (pin "2") (pinfunction "2_2") (pintype "passive"))
      (node (ref "U10") (pin "1") (pinfunction "ADJUST_1") (pintype "passive"))
    )
    (net (code "109") (name "Net-(U10-VOUT)") (class "Default")
      (node (ref "R10") (pin "1") (pinfunction "1_1") (pintype "passive"))
      (node (ref "U10") (pin "2") (pinfunction "VOUT_2") (pintype "output"))
    )
    (net (code "110") (name "Net-(U11-ADJUST)") (class "Default")
      (node (ref "J9") (pin "1") (pinfunction "1_1") (pintype "passive"))
      (node (ref "R11") (pin "2") (pinfunction "2_2") (pintype "passive"))
      (node (ref "U11") (pin "1") (pinfunction "ADJUST_1") (pintype "passive"))
    )
    (net (code "111") (name "Net-(U11-VOUT)") (class "Default")
      (node (ref "R11") (pin "1") (pinfunction "1_1") (pintype "passive"))
      (node (ref "U11") (pin "2") (pinfunction "VOUT_2") (pintype "output"))
    )
    (net (code "112") (name "Net-(U12-ADJUST)") (class "Default")
      (node (ref "J10") (pin "1") (pinfunction "1_1") (pintype "passive"))
      (node (ref "R12") (pin "2") (pinfunction "2_2") (pintype "passive"))
      (node (ref "U12") (pin "1") (pinfunction "ADJUST_1") (pintype "passive"))
    )
    (net (code "113") (name "Net-(U12-VOUT)") (class "Default")
      (node (ref "R12") (pin "1") (pinfunction "1_1") (pintype "passive"))
      (node (ref "U12") (pin "2") (pinfunction "VOUT_2") (pintype "output"))
    )
    (net (code "114") (name "Net-(U13-D)") (class "Default")
      (node (ref "J7") (pin "2") (pinfunction "2_2") (pintype "passive"))
      (node (ref "U13") (pin "2") (pinfunction "D_2") (pintype "passive"))
    )
    (net (code "115") (name "Net-(U13-G)") (class "Default")
      (node (ref "R13") (pin "2") (pinfunction "2_2") (pintype "passive"))
      (node (ref "U13") (pin "1") (pinfunction "G_1") (pintype "passive"))
    )
    (net (code "116") (name "Net-(U14-D)") (class "Default")
      (node (ref "J8") (pin "2") (pinfunction "2_2") (pintype "passive"))
      (node (ref "U14") (pin "2") (pinfunction "D_2") (pintype "passive"))
    )
    (net (code "117") (name "Net-(U14-G)") (class "Default")
      (node (ref "R14") (pin "2") (pinfunction "2_2") (pintype "passive"))
      (node (ref "U14") (pin "1") (pinfunction "G_1") (pintype "passive"))
    )
    (net (code "118") (name "Net-(U15-D)") (class "Default")
      (node (ref "J9") (pin "2") (pinfunction "2_2") (pintype "passive"))
      (node (ref "U15") (pin "2") (pinfunction "D_2") (pintype "passive"))
    )
    (net (code "119") (name "Net-(U15-G)") (class "Default")
      (node (ref "R15") (pin "2") (pinfunction "2_2") (pintype "passive"))
      (node (ref "U15") (pin "1") (pinfunction "G_1") (pintype "passive"))
    )
    (net (code "120") (name "Net-(U16-D)") (class "Default")
      (node (ref "J10") (pin "2") (pinfunction "2_2") (pintype "passive"))
      (node (ref "U16") (pin "2") (pinfunction "D_2") (pintype "passive"))
    )
    (net (code "121") (name "Net-(U16-G)") (class "Default")
      (node (ref "R16") (pin "2") (pinfunction "2_2") (pintype "passive"))
      (node (ref "U16") (pin "1") (pinfunction "G_1") (pintype "passive"))
    )
    (net (code "122") (name "Vled") (class "Default")
      (node (ref "J2") (pin "1") (pinfunction "1_1") (pintype "passive"))
      (node (ref "U1") (pin "3") (pinfunction "VIN_3") (pintype "input"))
      (node (ref "U10") (pin "3") (pinfunction "VIN_3") (pintype "input"))
      (node (ref "U11") (pin "3") (pinfunction "VIN_3") (pintype "input"))
      (node (ref "U12") (pin "3") (pinfunction "VIN_3") (pintype "input"))
      (node (ref "U2") (pin "3") (pinfunction "VIN_3") (pintype "input"))
      (node (ref "U3") (pin "3") (pinfunction "VIN_3") (pintype "input"))
      (node (ref "U4") (pin "3") (pinfunction "VIN_3") (pintype "input"))
      (node (ref "U9") (pin "3") (pinfunction "VIN_3") (pintype "input"))
    )
  )
)
